# PCEMouse_rev_B.net
KiCad netlist of a schematic drawn in EAGLE
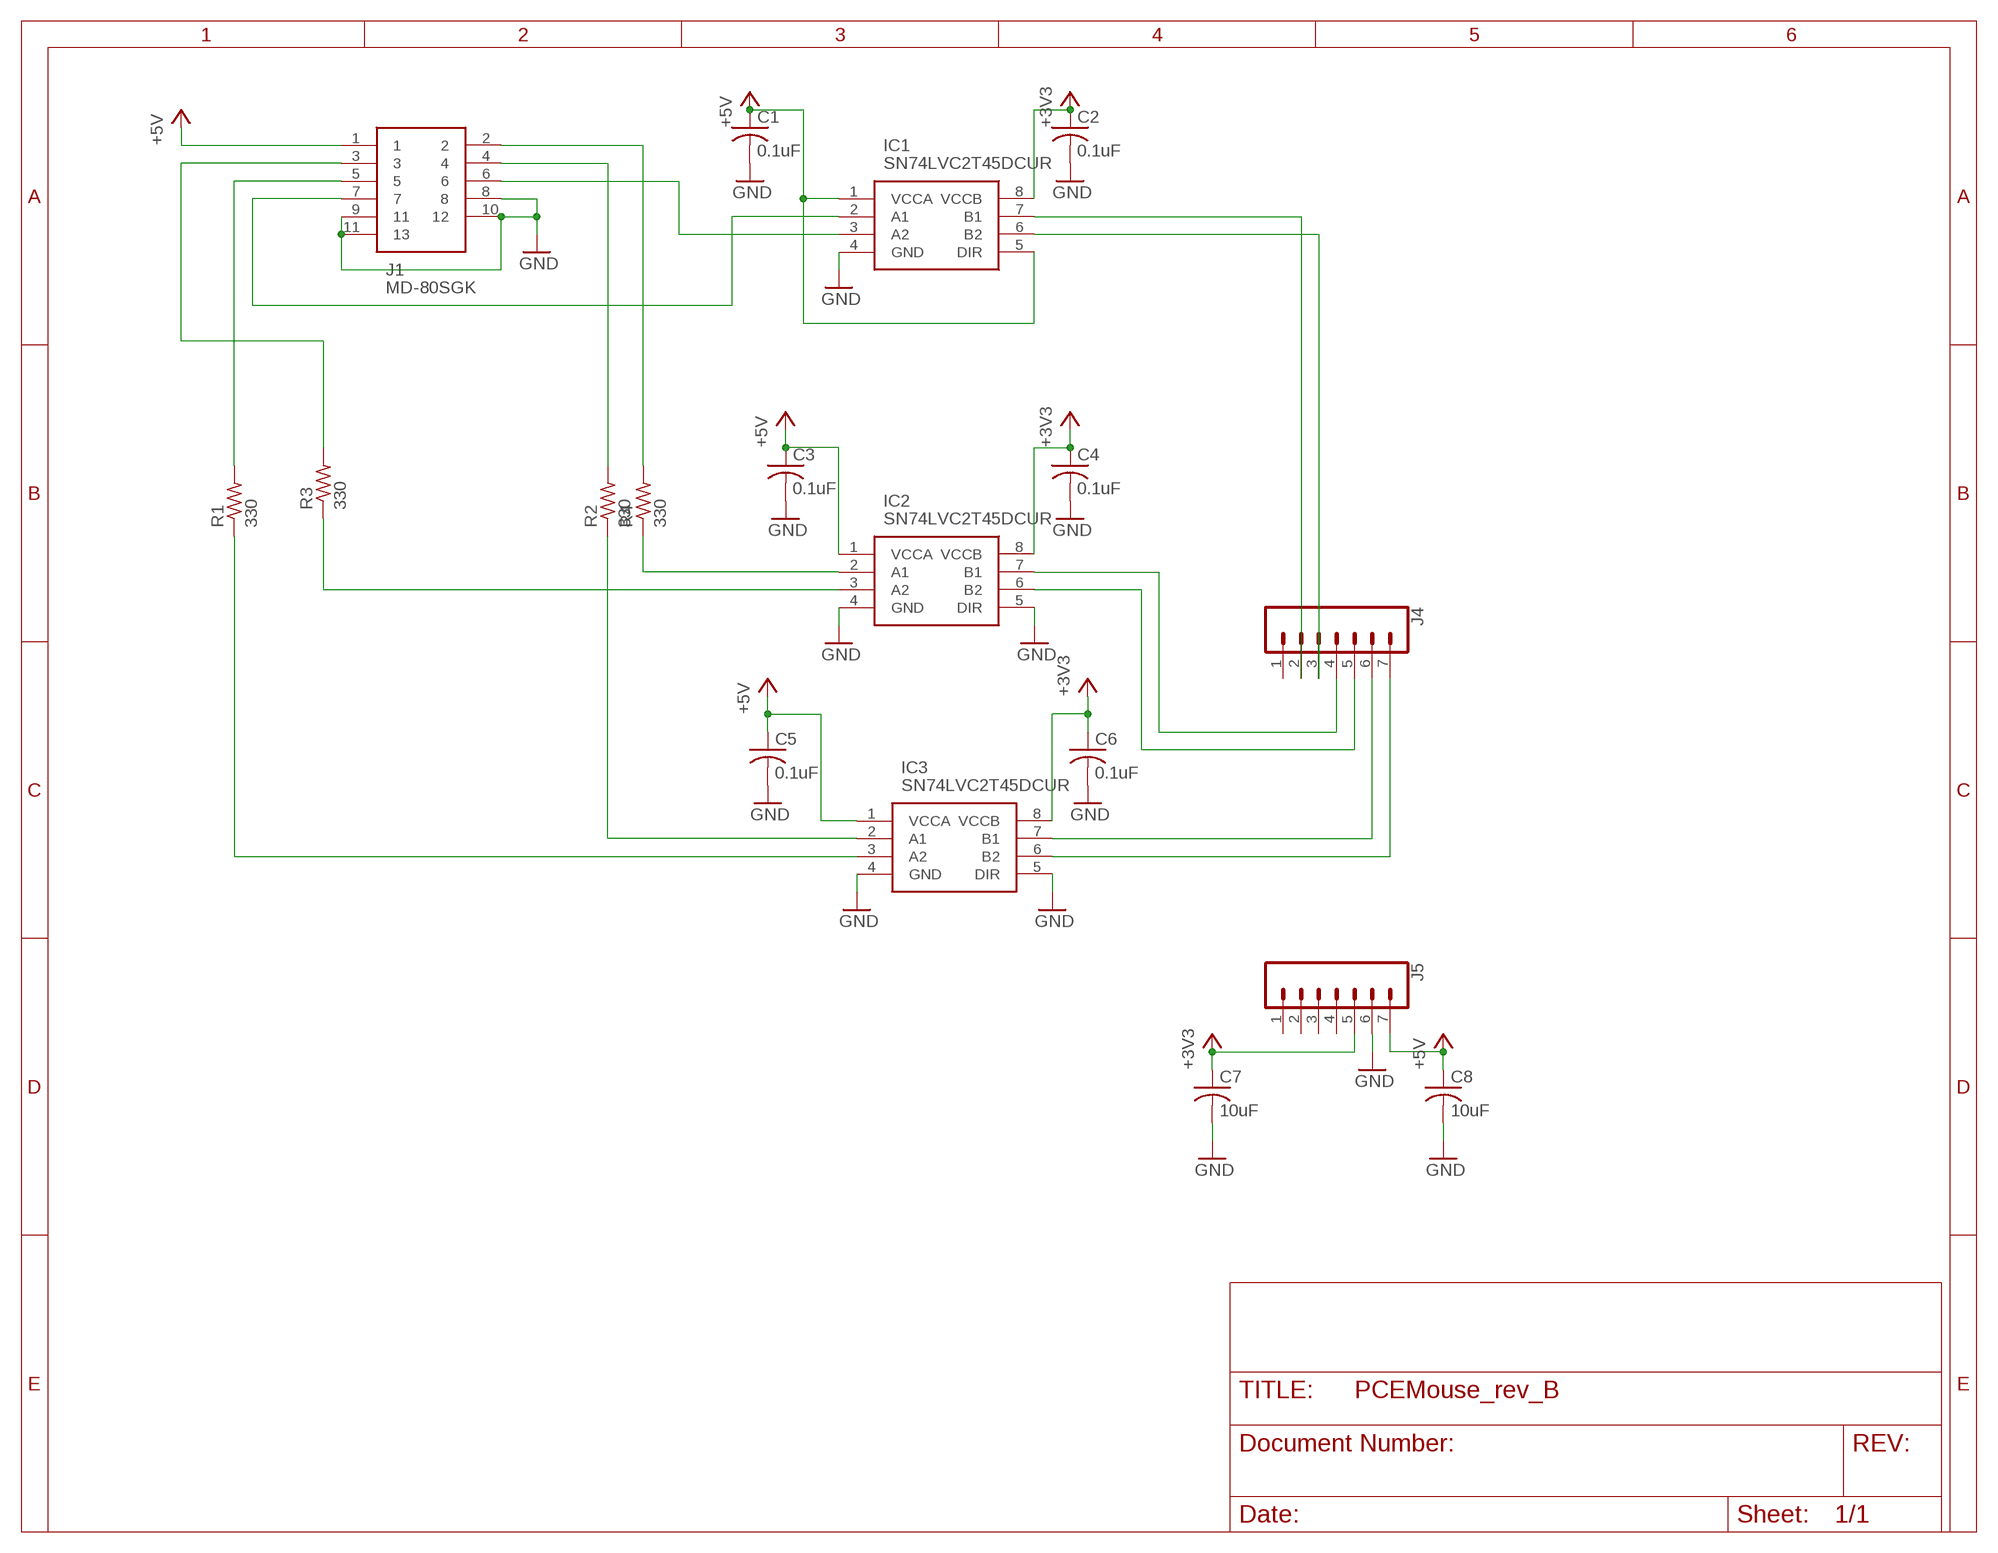
[diagram p0: schematic, sheet 1]

(export (version "E")
  (design (tool "Eeschema 10.0.6"))
  (components
    (comp (ref "C1")
      (value "0.1uF")
      (footprint "eagle-import:C0402")
      (libsource (lib "eagle-import") (part "C-USC0402"))
    )
    (comp (ref "C2")
      (value "0.1uF")
      (footprint "eagle-import:C0402")
      (libsource (lib "eagle-import") (part "C-USC0402"))
    )
    (comp (ref "C3")
      (value "0.1uF")
      (footprint "eagle-import:C0402")
      (libsource (lib "eagle-import") (part "C-USC0402"))
    )
    (comp (ref "C4")
      (value "0.1uF")
      (footprint "eagle-import:C0402")
      (libsource (lib "eagle-import") (part "C-USC0402"))
    )
    (comp (ref "C5")
      (value "0.1uF")
      (footprint "eagle-import:C0402")
      (libsource (lib "eagle-import") (part "C-USC0402"))
    )
    (comp (ref "C6")
      (value "0.1uF")
      (footprint "eagle-import:C0402")
      (libsource (lib "eagle-import") (part "C-USC0402"))
    )
    (comp (ref "C7")
      (value "10uF")
      (footprint "eagle-import:C0805")
      (libsource (lib "eagle-import") (part "C-USC0805"))
    )
    (comp (ref "C8")
      (value "10uF")
      (footprint "eagle-import:C0805")
      (libsource (lib "eagle-import") (part "C-USC0805"))
    )
    (comp (ref "IC1")
      (value "SN74LVC2T45DCUR")
      (footprint "eagle-import:SOP50P310X90-8N")
      (fields (field (name "MOUSER_PART_NUMBER") "595-SN74LVC2T45DCUR"))
      (libsource (lib "eagle-import") (part "SN74LVC2T45DCUR"))
    )
    (comp (ref "IC2")
      (value "SN74LVC2T45DCUR")
      (footprint "eagle-import:SOP50P310X90-8N")
      (fields (field (name "MOUSER_PART_NUMBER") "595-SN74LVC2T45DCUR"))
      (libsource (lib "eagle-import") (part "SN74LVC2T45DCUR"))
    )
    (comp (ref "IC3")
      (value "SN74LVC2T45DCUR")
      (footprint "eagle-import:SOP50P310X90-8N")
      (fields (field (name "MOUSER_PART_NUMBER") "595-SN74LVC2T45DCUR"))
      (libsource (lib "eagle-import") (part "SN74LVC2T45DCUR"))
    )
    (comp (ref "J1")
      (value "MD-80SGK")
      (footprint "eagle-import:MD80SGK")
      (fields (field (name "MOUSER_PART_NUMBER") "490-MD-80SGK"))
      (libsource (lib "eagle-import") (part "MD-80SGK"))
    )
    (comp (ref "J4")
      (value "CONN_07NO_SILK")
      (footprint "eagle-import:1X07_NO_SILK")
      (libsource (lib "eagle-import") (part "CONN_07NO_SILK"))
    )
    (comp (ref "J5")
      (value "CONN_07NO_SILK")
      (footprint "eagle-import:1X07_NO_SILK")
      (libsource (lib "eagle-import") (part "CONN_07NO_SILK"))
    )
    (comp (ref "R1")
      (value "330")
      (footprint "eagle-import:R0402")
      (libsource (lib "eagle-import") (part "R-US_R0402"))
    )
    (comp (ref "R2")
      (value "330")
      (footprint "eagle-import:R0402")
      (libsource (lib "eagle-import") (part "R-US_R0402"))
    )
    (comp (ref "R3")
      (value "330")
      (footprint "eagle-import:R0402")
      (libsource (lib "eagle-import") (part "R-US_R0402"))
    )
    (comp (ref "R4")
      (value "330")
      (footprint "eagle-import:R0402")
      (libsource (lib "eagle-import") (part "R-US_R0402"))
    )
  )
  (nets
    (net (code "1") (name "+3V3") (class "Default")
      (node (ref "C2") (pin "1") (pinfunction "1_1") (pintype "passive"))
      (node (ref "C4") (pin "1") (pinfunction "1_1") (pintype "passive"))
      (node (ref "C6") (pin "1") (pinfunction "1_1") (pintype "passive"))
      (node (ref "C7") (pin "1") (pinfunction "1_1") (pintype "passive"))
      (node (ref "IC1") (pin "8") (pinfunction "VCCB_8") (pintype "bidirectional"))
      (node (ref "IC2") (pin "8") (pinfunction "VCCB_8") (pintype "bidirectional"))
      (node (ref "IC3") (pin "8") (pinfunction "VCCB_8") (pintype "bidirectional"))
      (node (ref "J5") (pin "5") (pinfunction "5_5") (pintype "passive"))
    )
    (net (code "2") (name "+5V") (class "Default")
      (node (ref "C1") (pin "1") (pinfunction "1_1") (pintype "passive"))
      (node (ref "C3") (pin "1") (pinfunction "1_1") (pintype "passive"))
      (node (ref "C5") (pin "1") (pinfunction "1_1") (pintype "passive"))
      (node (ref "C8") (pin "1") (pinfunction "1_1") (pintype "passive"))
      (node (ref "IC1") (pin "1") (pinfunction "VCCA_1") (pintype "bidirectional"))
      (node (ref "IC1") (pin "5") (pinfunction "DIR_5") (pintype "bidirectional"))
      (node (ref "IC2") (pin "1") (pinfunction "VCCA_1") (pintype "bidirectional"))
      (node (ref "IC3") (pin "1") (pinfunction "VCCA_1") (pintype "bidirectional"))
      (node (ref "J1") (pin "1") (pinfunction "1_1") (pintype "bidirectional"))
      (node (ref "J5") (pin "7") (pinfunction "7_7") (pintype "passive"))
    )
    (net (code "3") (name "GND") (class "Default")
      (node (ref "C1") (pin "2") (pinfunction "2_2") (pintype "passive"))
      (node (ref "C2") (pin "2") (pinfunction "2_2") (pintype "passive"))
      (node (ref "C3") (pin "2") (pinfunction "2_2") (pintype "passive"))
      (node (ref "C4") (pin "2") (pinfunction "2_2") (pintype "passive"))
      (node (ref "C5") (pin "2") (pinfunction "2_2") (pintype "passive"))
      (node (ref "C6") (pin "2") (pinfunction "2_2") (pintype "passive"))
      (node (ref "C7") (pin "2") (pinfunction "2_2") (pintype "passive"))
      (node (ref "C8") (pin "2") (pinfunction "2_2") (pintype "passive"))
      (node (ref "IC1") (pin "4") (pinfunction "GND_4") (pintype "bidirectional"))
      (node (ref "IC2") (pin "4") (pinfunction "GND_4") (pintype "bidirectional"))
      (node (ref "IC2") (pin "5") (pinfunction "DIR_5") (pintype "bidirectional"))
      (node (ref "IC3") (pin "4") (pinfunction "GND_4") (pintype "bidirectional"))
      (node (ref "IC3") (pin "5") (pinfunction "DIR_5") (pintype "bidirectional"))
      (node (ref "J1") (pin "10") (pinfunction "12_10") (pintype "bidirectional"))
      (node (ref "J1") (pin "11") (pinfunction "13_11") (pintype "bidirectional"))
      (node (ref "J1") (pin "8") (pinfunction "8_8") (pintype "bidirectional"))
      (node (ref "J1") (pin "9") (pinfunction "11_9") (pintype "bidirectional"))
      (node (ref "J5") (pin "6") (pinfunction "6_6") (pintype "passive"))
    )
    (net (code "4") (name "Net-(IC1-A1)") (class "Default")
      (node (ref "IC1") (pin "2") (pinfunction "A1_2") (pintype "bidirectional"))
      (node (ref "J1") (pin "7") (pinfunction "7_7") (pintype "bidirectional"))
    )
    (net (code "5") (name "Net-(IC1-A2)") (class "Default")
      (node (ref "IC1") (pin "3") (pinfunction "A2_3") (pintype "bidirectional"))
      (node (ref "J1") (pin "6") (pinfunction "6_6") (pintype "bidirectional"))
    )
    (net (code "6") (name "Net-(IC1-B1)") (class "Default")
      (node (ref "IC1") (pin "7") (pinfunction "B1_7") (pintype "bidirectional"))
      (node (ref "J4") (pin "2") (pinfunction "2_2") (pintype "passive"))
    )
    (net (code "7") (name "Net-(IC1-B2)") (class "Default")
      (node (ref "IC1") (pin "6") (pinfunction "B2_6") (pintype "bidirectional"))
      (node (ref "J4") (pin "3") (pinfunction "3_3") (pintype "passive"))
    )
    (net (code "8") (name "Net-(IC2-A1)") (class "Default")
      (node (ref "IC2") (pin "2") (pinfunction "A1_2") (pintype "bidirectional"))
      (node (ref "R4") (pin "1") (pinfunction "1_1") (pintype "passive"))
    )
    (net (code "9") (name "Net-(IC2-A2)") (class "Default")
      (node (ref "IC2") (pin "3") (pinfunction "A2_3") (pintype "bidirectional"))
      (node (ref "R3") (pin "1") (pinfunction "1_1") (pintype "passive"))
    )
    (net (code "10") (name "Net-(IC2-B1)") (class "Default")
      (node (ref "IC2") (pin "7") (pinfunction "B1_7") (pintype "bidirectional"))
      (node (ref "J4") (pin "4") (pinfunction "4_4") (pintype "passive"))
    )
    (net (code "11") (name "Net-(IC2-B2)") (class "Default")
      (node (ref "IC2") (pin "6") (pinfunction "B2_6") (pintype "bidirectional"))
      (node (ref "J4") (pin "5") (pinfunction "5_5") (pintype "passive"))
    )
    (net (code "12") (name "Net-(IC3-A1)") (class "Default")
      (node (ref "IC3") (pin "2") (pinfunction "A1_2") (pintype "bidirectional"))
      (node (ref "R2") (pin "1") (pinfunction "1_1") (pintype "passive"))
    )
    (net (code "13") (name "Net-(IC3-A2)") (class "Default")
      (node (ref "IC3") (pin "3") (pinfunction "A2_3") (pintype "bidirectional"))
      (node (ref "R1") (pin "1") (pinfunction "1_1") (pintype "passive"))
    )
    (net (code "14") (name "Net-(IC3-B1)") (class "Default")
      (node (ref "IC3") (pin "7") (pinfunction "B1_7") (pintype "bidirectional"))
      (node (ref "J4") (pin "6") (pinfunction "6_6") (pintype "passive"))
    )
    (net (code "15") (name "Net-(IC3-B2)") (class "Default")
      (node (ref "IC3") (pin "6") (pinfunction "B2_6") (pintype "bidirectional"))
      (node (ref "J4") (pin "7") (pinfunction "7_7") (pintype "passive"))
    )
    (net (code "16") (name "Net-(J1-Pad2)") (class "Default")
      (node (ref "J1") (pin "2") (pinfunction "2_2") (pintype "bidirectional"))
      (node (ref "R4") (pin "2") (pinfunction "2_2") (pintype "passive"))
    )
    (net (code "17") (name "Net-(J1-Pad3)") (class "Default")
      (node (ref "J1") (pin "3") (pinfunction "3_3") (pintype "bidirectional"))
      (node (ref "R3") (pin "2") (pinfunction "2_2") (pintype "passive"))
    )
    (net (code "18") (name "Net-(J1-Pad4)") (class "Default")
      (node (ref "J1") (pin "4") (pinfunction "4_4") (pintype "bidirectional"))
      (node (ref "R2") (pin "2") (pinfunction "2_2") (pintype "passive"))
    )
    (net (code "19") (name "Net-(J1-Pad5)") (class "Default")
      (node (ref "J1") (pin "5") (pinfunction "5_5") (pintype "bidirectional"))
      (node (ref "R1") (pin "2") (pinfunction "2_2") (pintype "passive"))
    )
    (net (code "20") (name "unconnected-(J4-Pad1)") (class "Default")
      (node (ref "J4") (pin "1") (pinfunction "1_1") (pintype "passive"))
    )
    (net (code "21") (name "unconnected-(J5-Pad1)") (class "Default")
      (node (ref "J5") (pin "1") (pinfunction "1_1") (pintype "passive"))
    )
    (net (code "22") (name "unconnected-(J5-Pad2)") (class "Default")
      (node (ref "J5") (pin "2") (pinfunction "2_2") (pintype "passive"))
    )
    (net (code "23") (name "unconnected-(J5-Pad3)") (class "Default")
      (node (ref "J5") (pin "3") (pinfunction "3_3") (pintype "passive"))
    )
    (net (code "24") (name "unconnected-(J5-Pad4)") (class "Default")
      (node (ref "J5") (pin "4") (pinfunction "4_4") (pintype "passive"))
    )
  )
)
